# 22_-_SD_CARD_SPI_FLASH_EEPROM.net
KiCad netlist of a schematic drawn in Altium Designer
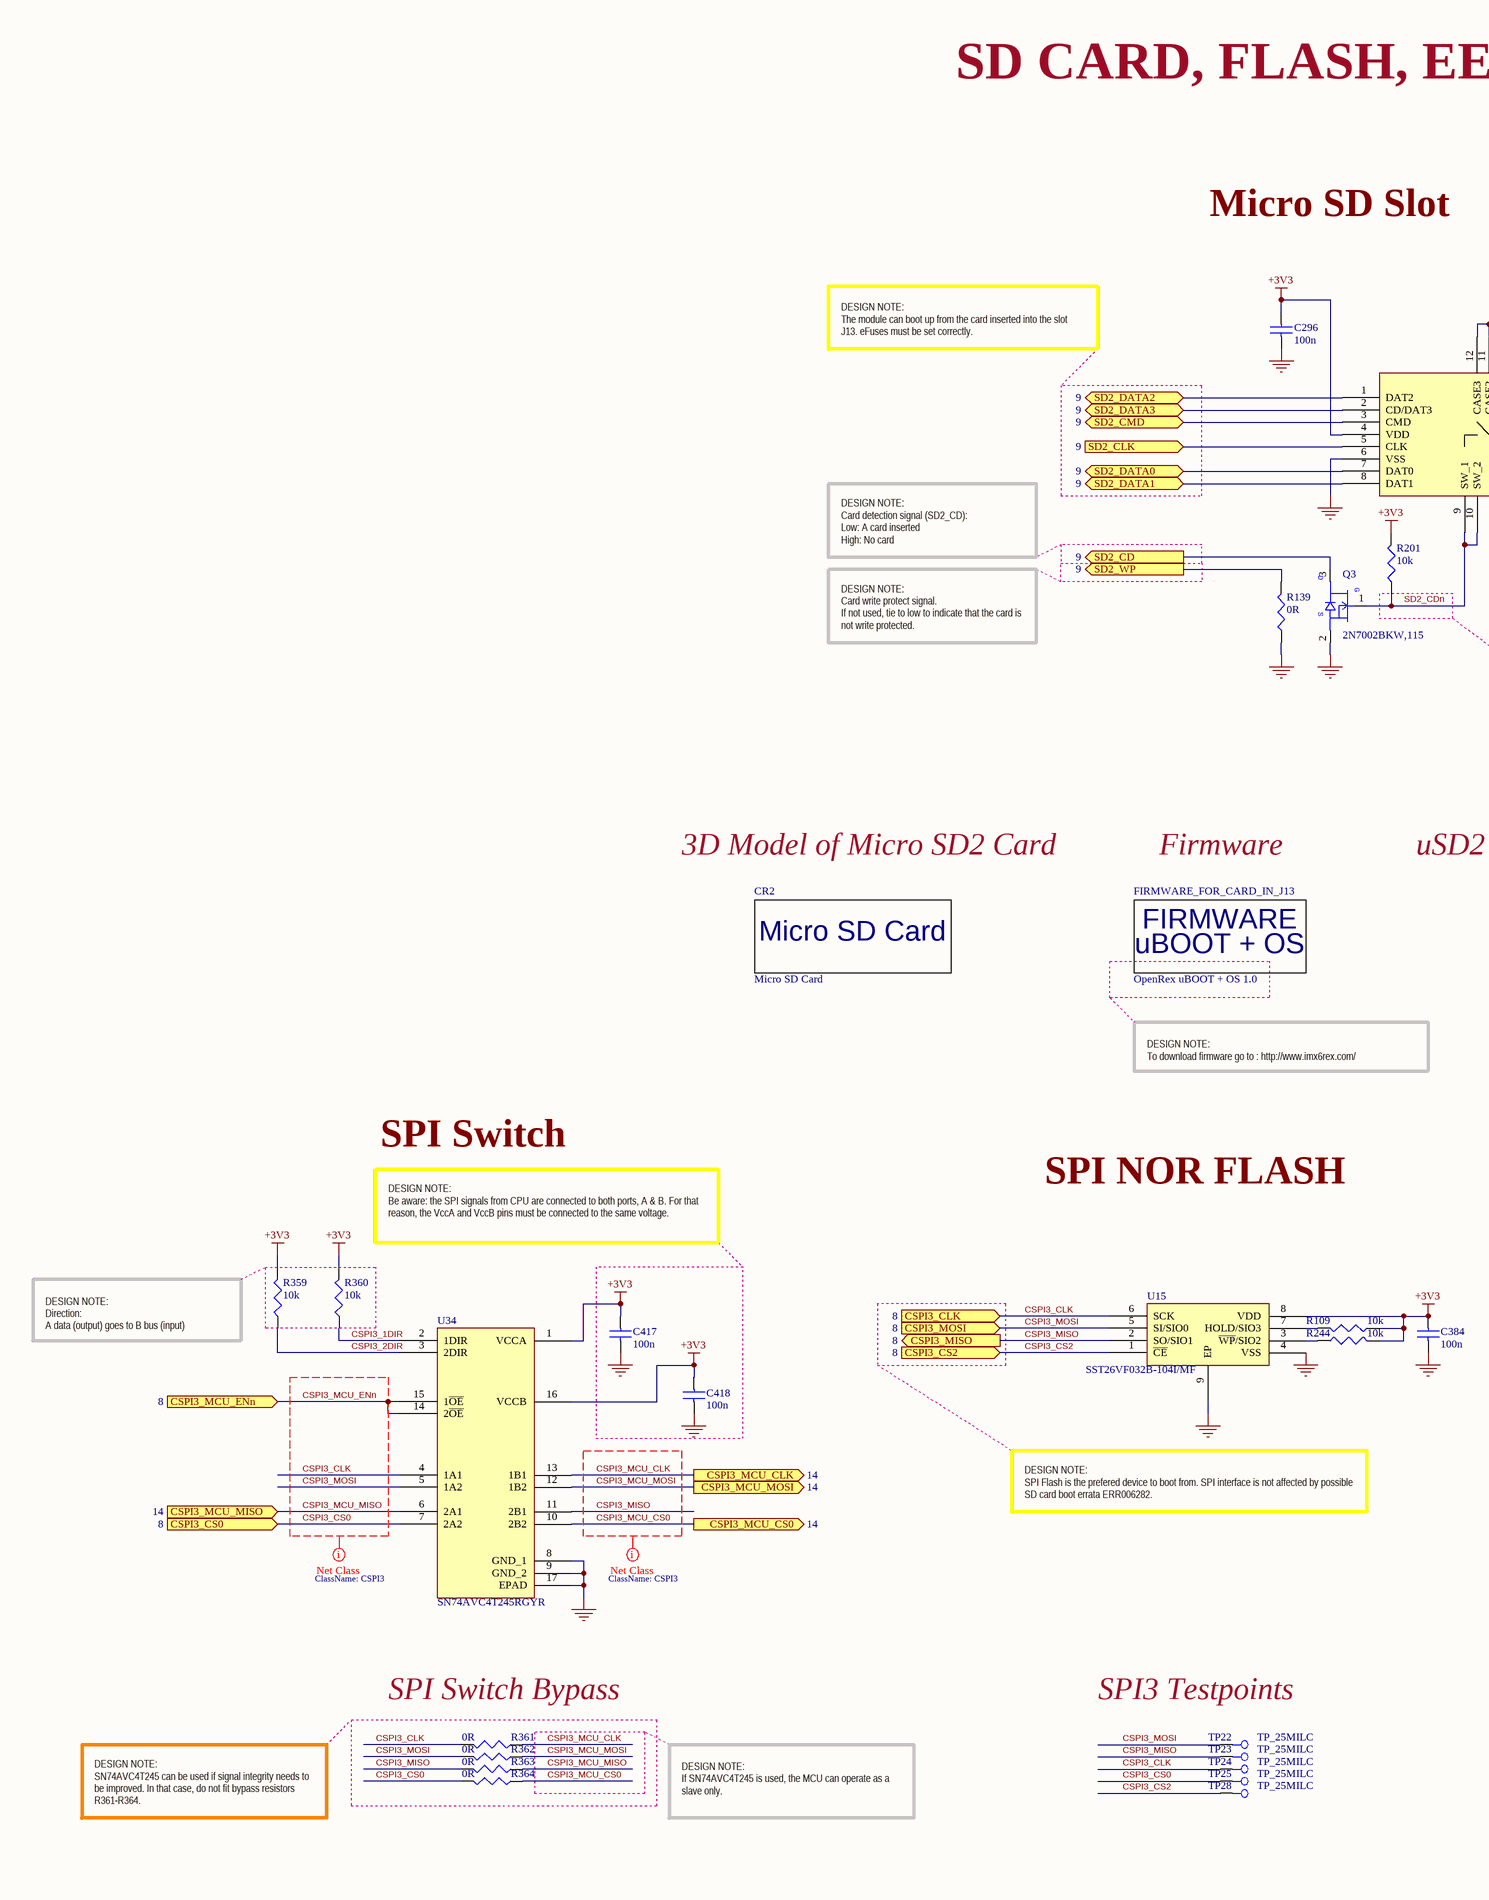
[diagram p0: [22] - SD CARD, SPI, FLASH, EEPROM,.SchDoc, left]
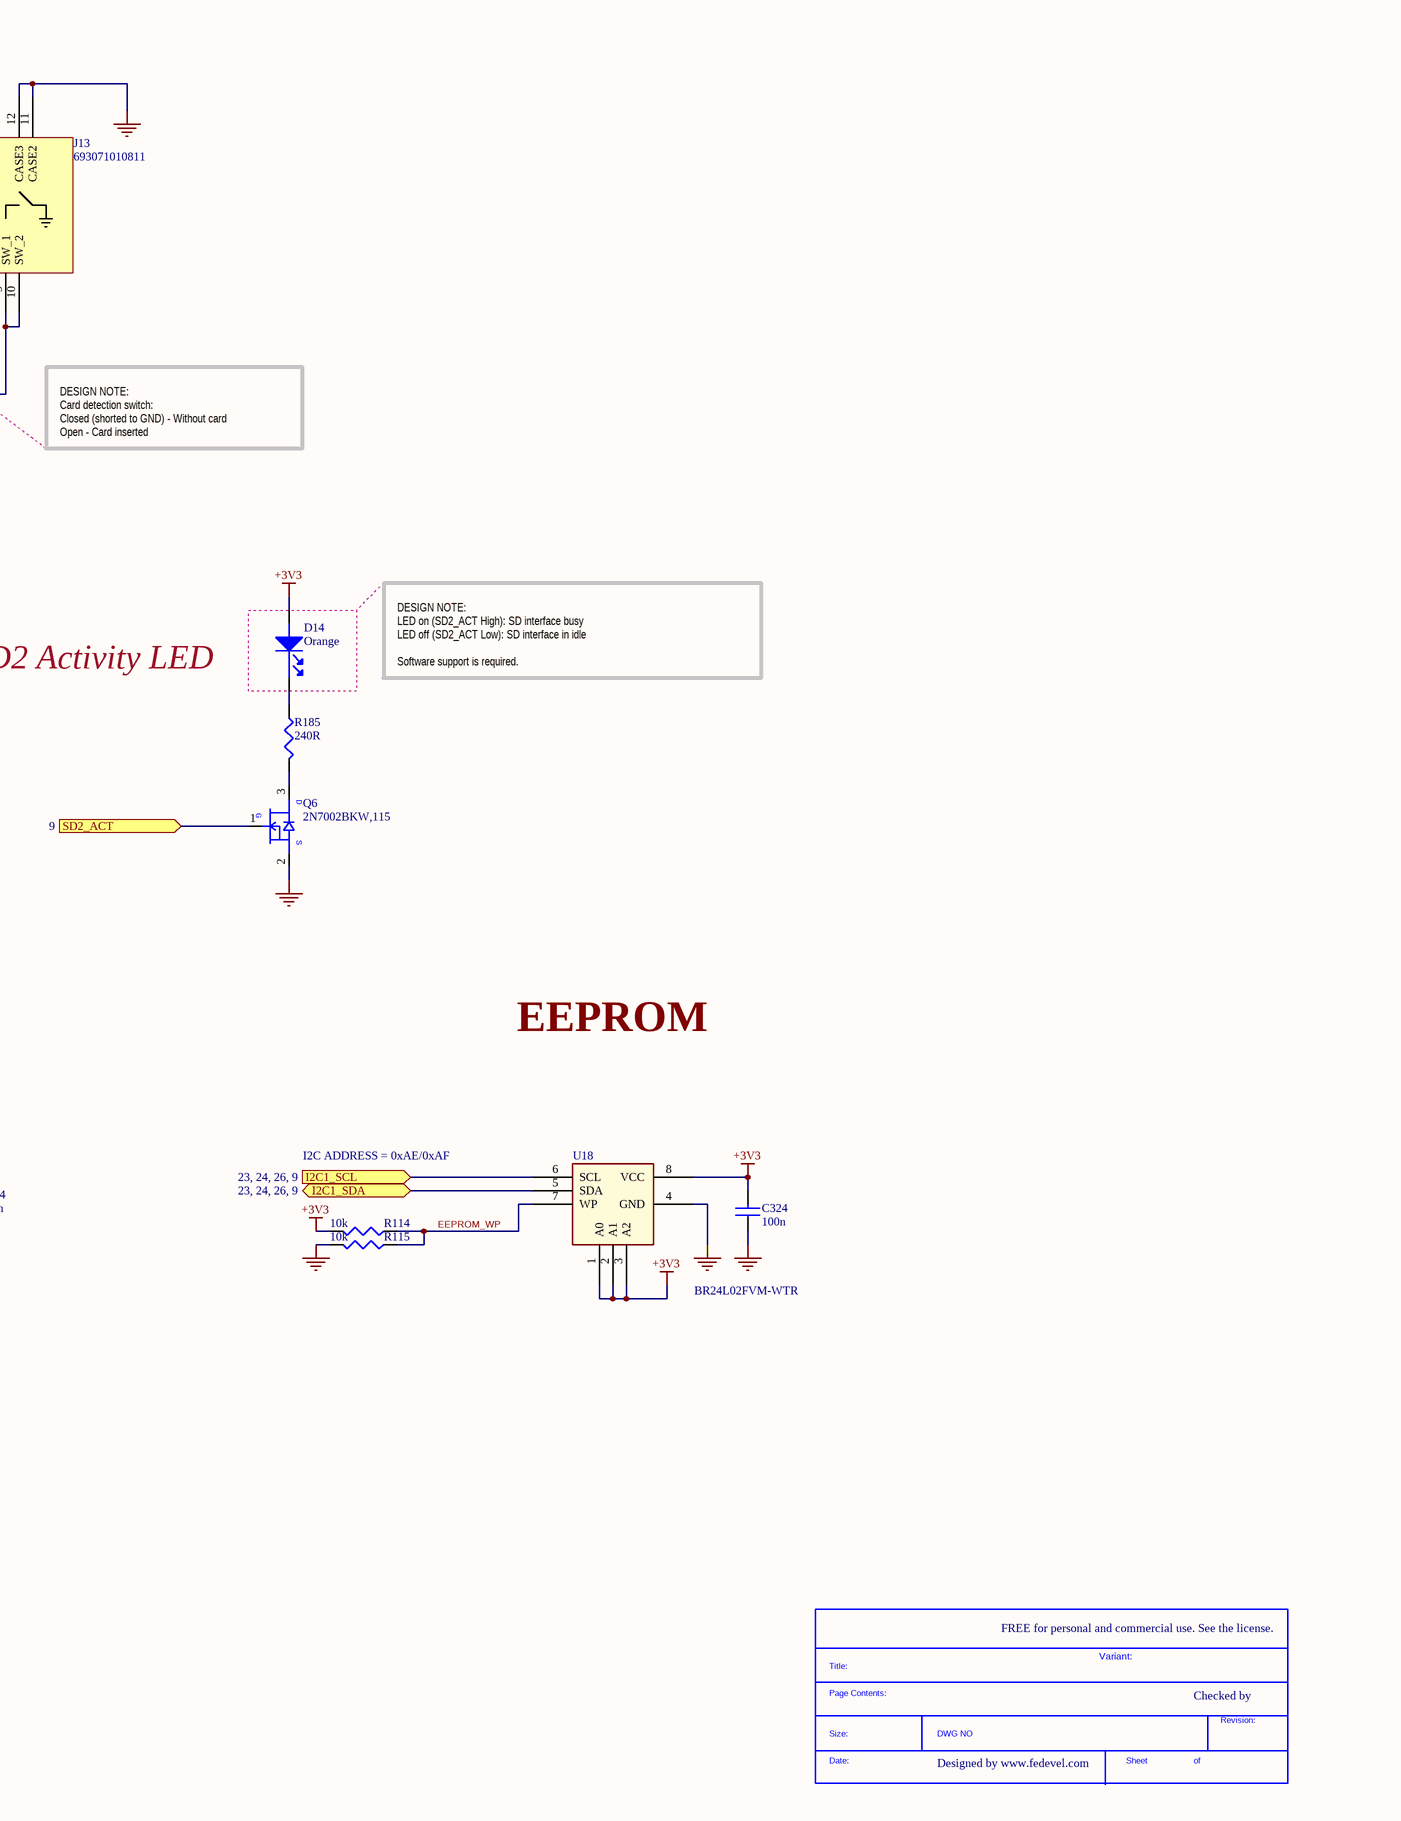
[diagram p1: [22] - SD CARD, SPI, FLASH, EEPROM,.SchDoc, right]

(export (version "E")
  (design (tool "Eeschema 10.0.6"))
  (components
    (comp (ref "C296")
      (value "100n")
      (footprint "C0402")
      (description "CAP CER .10UF 50V X5R 10% 0402")
      (fields
        (field (name "MANUFACTURER") "TDK Corporation")
        (field (name "MANUFACTURER PART NUMBER") "C1005X5R1H104K")
      )
      (libsource (lib "Integrated_Library_FEDEVEL_APR_2015") (part "C1005X5R1H104K"))
    )
    (comp (ref "C324")
      (value "100n")
      (footprint "C0402")
      (description "CAP CER .10UF 50V X5R 10% 0402")
      (fields
        (field (name "MANUFACTURER") "TDK Corporation")
        (field (name "MANUFACTURER PART NUMBER") "C1005X5R1H104K")
      )
      (libsource (lib "Integrated_Library_FEDEVEL_APR_2015") (part "C1005X5R1H104K"))
    )
    (comp (ref "C384")
      (value "100n")
      (footprint "C0402")
      (description "CAP CER .10UF 50V X5R 10% 0402")
      (fields
        (field (name "MANUFACTURER") "TDK Corporation")
        (field (name "MANUFACTURER PART NUMBER") "C1005X5R1H104K")
      )
      (libsource (lib "Integrated_Library_FEDEVEL_APR_2015") (part "C1005X5R1H104K"))
    )
    (comp (ref "C417")
      (value "100n")
      (footprint "C0402")
      (description "CAP CER .10UF 50V X5R 10% 0402")
      (fields
        (field (name "MANUFACTURER") "TDK Corporation")
        (field (name "MANUFACTURER PART NUMBER") "C1005X5R1H104K")
      )
      (libsource (lib "Integrated_Library_FEDEVEL_APR_2015") (part "C1005X5R1H104K"))
    )
    (comp (ref "C418")
      (value "100n")
      (footprint "C0402")
      (description "CAP CER .10UF 50V X5R 10% 0402")
      (fields
        (field (name "MANUFACTURER") "TDK Corporation")
        (field (name "MANUFACTURER PART NUMBER") "C1005X5R1H104K")
      )
      (libsource (lib "Integrated_Library_FEDEVEL_APR_2015") (part "C1005X5R1H104K"))
    )
    (comp (ref "CR2")
      (value "Micro SD Card")
      (footprint "Micro_SD_card")
      (description "Card Micro SD")
      (fields (field (name ".CREATOR") "MM"))
      (libsource (lib "Integrated_Library_FEDEVEL_APR_2015") (part "Card_Micro_SD"))
    )
    (comp (ref "D14")
      (value "Orange")
      (footprint "LED_0603")
      (description "LED SMARTLED ORANGE 606NM 0603")
      (fields
        (field (name "MANUFACTURER") "OSRAM Opto Semiconductors Inc")
        (field (name "MANUFACTURER PART NUMBER") "LO L29K-H2K1-24-Z")
      )
      (libsource (lib "Integrated_Library_FEDEVEL_APR_2015") (part "LO L29K-H2K1-24-Z"))
    )
    (comp (ref "FIRMWARE_FOR_CARD_IN_J13")
      (value "OpenRex uBOOT + OS 1.0")
      (fields (field (name ".CREATOR") "MM") (field (name ".CHECKED SCH") "MM"))
      (libsource (lib "Integrated_Library_FEDEVEL_APR_2015") (part "FIRMWARE_OpenRex_uBOOT_OS 1.0"))
    )
    (comp (ref "J13")
      (value "693071010811")
      (footprint "693071010811")
      (description "CONN MICRO SD 8 POS SMD")
      (fields (field (name "MANUFACTURER") "Wurth Electronics Inc") (field (name ".CREATOR") "MM"))
      (libsource (lib "Integrated_Library_FEDEVEL_APR_2015") (part "693071010811"))
    )
    (comp (ref "Q3")
      (value "2N7002BKW,115")
      (footprint "SC70_SOT323")
      (description "MOSFET N-CH 60V 310MA SOT323")
      (fields (field (name "MANUFACTURER") "NXP Semiconductors"))
      (libsource (lib "Integrated_Library_FEDEVEL_APR_2015") (part "2N7002BKW,115"))
    )
    (comp (ref "Q6")
      (value "2N7002BKW,115")
      (footprint "SC70_SOT323")
      (description "MOSFET N-CH 60V 310MA SOT323")
      (fields (field (name "MANUFACTURER") "NXP Semiconductors"))
      (libsource (lib "Integrated_Library_FEDEVEL_APR_2015") (part "2N7002BKW,115"))
    )
    (comp (ref "R109")
      (value "10k")
      (footprint "R0402")
      (description "RES 10.0K OHM 1/16W 1% 0402 SMD")
      (fields
        (field (name "MANUFACTURER") "Yageo")
        (field (name "MANUFACTURER PART NUMBER") "RC0402FR-0710KL")
      )
      (libsource (lib "Integrated_Library_FEDEVEL_APR_2015") (part "RC0402FR-0710KL"))
    )
    (comp (ref "R114")
      (value "10k")
      (footprint "R0402")
      (description "RES 10.0K OHM 1/16W 1% 0402 SMD")
      (fields
        (field (name "MANUFACTURER") "Yageo")
        (field (name "MANUFACTURER PART NUMBER") "RC0402FR-0710KL")
      )
      (libsource (lib "Integrated_Library_FEDEVEL_APR_2015") (part "RC0402FR-0710KL"))
    )
    (comp (ref "R115")
      (value "10k")
      (footprint "R0402")
      (description "RES 10.0K OHM 1/16W 1% 0402 SMD")
      (fields
        (field (name "MANUFACTURER") "Yageo")
        (field (name "MANUFACTURER PART NUMBER") "RC0402FR-0710KL")
      )
      (libsource (lib "Integrated_Library_FEDEVEL_APR_2015") (part "RC0402FR-0710KL"))
    )
    (comp (ref "R139")
      (value "0R")
      (footprint "R0402")
      (description "RES 0.0 OHM 1/16W 0402 SMD")
      (fields
        (field (name "MANUFACTURER") "Yageo")
        (field (name "MANUFACTURER PART NUMBER") "RC0402JR-070RL")
      )
      (libsource (lib "Integrated_Library_FEDEVEL_APR_2015") (part "RC0402JR-070RL"))
    )
    (comp (ref "R185")
      (value "240R")
      (footprint "R0402")
      (description "RES TF 240 OHM 1% 0.0625W 0402")
      (fields
        (field (name "MANUFACTURER") "Stackpole Electronics Inc")
        (field (name "MANUFACTURER PART NUMBER") "RMCF0402FT240R")
      )
      (libsource (lib "Integrated_Library_FEDEVEL_APR_2015") (part "RMCF0402FT240R"))
    )
    (comp (ref "R201")
      (value "10k")
      (footprint "R0402")
      (description "RES 10.0K OHM 1/16W 1% 0402 SMD")
      (fields
        (field (name "MANUFACTURER") "Yageo")
        (field (name "MANUFACTURER PART NUMBER") "RC0402FR-0710KL")
      )
      (libsource (lib "Integrated_Library_FEDEVEL_APR_2015") (part "RC0402FR-0710KL"))
    )
    (comp (ref "R244")
      (value "10k")
      (footprint "R0402")
      (description "RES 10.0K OHM 1/16W 1% 0402 SMD")
      (fields
        (field (name "MANUFACTURER") "Yageo")
        (field (name "MANUFACTURER PART NUMBER") "RC0402FR-0710KL")
      )
      (libsource (lib "Integrated_Library_FEDEVEL_APR_2015") (part "RC0402FR-0710KL"))
    )
    (comp (ref "R359")
      (value "10k")
      (footprint "R0402")
      (description "RES 10.0K OHM 1/16W 1% 0402 SMD")
      (fields
        (field (name "MANUFACTURER") "Yageo")
        (field (name "MANUFACTURER PART NUMBER") "RC0402FR-0710KL")
      )
      (libsource (lib "Integrated_Library_FEDEVEL_APR_2015") (part "RC0402FR-0710KL"))
    )
    (comp (ref "R360")
      (value "10k")
      (footprint "R0402")
      (description "RES 10.0K OHM 1/16W 1% 0402 SMD")
      (fields
        (field (name "MANUFACTURER") "Yageo")
        (field (name "MANUFACTURER PART NUMBER") "RC0402FR-0710KL")
      )
      (libsource (lib "Integrated_Library_FEDEVEL_APR_2015") (part "RC0402FR-0710KL"))
    )
    (comp (ref "R361")
      (value "0R")
      (footprint "R0402")
      (description "RES 0.0 OHM 1/16W 0402 SMD")
      (fields
        (field (name "MANUFACTURER") "Yageo")
        (field (name "MANUFACTURER PART NUMBER") "RC0402JR-070RL")
      )
      (libsource (lib "Integrated_Library_FEDEVEL_APR_2015") (part "RC0402JR-070RL"))
    )
    (comp (ref "R362")
      (value "0R")
      (footprint "R0402")
      (description "RES 0.0 OHM 1/16W 0402 SMD")
      (fields
        (field (name "MANUFACTURER") "Yageo")
        (field (name "MANUFACTURER PART NUMBER") "RC0402JR-070RL")
      )
      (libsource (lib "Integrated_Library_FEDEVEL_APR_2015") (part "RC0402JR-070RL"))
    )
    (comp (ref "R363")
      (value "0R")
      (footprint "R0402")
      (description "RES 0.0 OHM 1/16W 0402 SMD")
      (fields
        (field (name "MANUFACTURER") "Yageo")
        (field (name "MANUFACTURER PART NUMBER") "RC0402JR-070RL")
      )
      (libsource (lib "Integrated_Library_FEDEVEL_APR_2015") (part "RC0402JR-070RL"))
    )
    (comp (ref "R364")
      (value "0R")
      (footprint "R0402")
      (description "RES 0.0 OHM 1/16W 0402 SMD")
      (fields
        (field (name "MANUFACTURER") "Yageo")
        (field (name "MANUFACTURER PART NUMBER") "RC0402JR-070RL")
      )
      (libsource (lib "Integrated_Library_FEDEVEL_APR_2015") (part "RC0402JR-070RL"))
    )
    (comp (ref "TP22")
      (value "TP_25MILC")
      (footprint "TP_25C")
      (description "Test Point 25mil")
      (libsource (lib "Integrated_Library_FEDEVEL_APR_2015") (part "TP_25MILC"))
    )
    (comp (ref "TP23")
      (value "TP_25MILC")
      (footprint "TP_25C")
      (description "Test Point 25mil")
      (libsource (lib "Integrated_Library_FEDEVEL_APR_2015") (part "TP_25MILC"))
    )
    (comp (ref "TP24")
      (value "TP_25MILC")
      (footprint "TP_25C")
      (description "Test Point 25mil")
      (libsource (lib "Integrated_Library_FEDEVEL_APR_2015") (part "TP_25MILC"))
    )
    (comp (ref "TP25")
      (value "TP_25MILC")
      (footprint "TP_25C")
      (description "Test Point 25mil")
      (libsource (lib "Integrated_Library_FEDEVEL_APR_2015") (part "TP_25MILC"))
    )
    (comp (ref "TP28")
      (value "TP_25MILC")
      (footprint "TP_25C")
      (description "Test Point 25mil")
      (libsource (lib "Integrated_Library_FEDEVEL_APR_2015") (part "TP_25MILC"))
    )
    (comp (ref "U15")
      (value "SST26VF032B-104I/MF")
      (footprint "WSON8_6X5MM")
      (description "IC FLASH 32MBIT")
      (fields
        (field (name "MANUFACTURER") "Microchip Technology")
        (field (name ".CREATOR") "MM")
        (field (name ".CHECKED SCH") "MM")
        (field (name ".CHECKED PCB") "MM, paper model not chceked")
      )
      (libsource (lib "Integrated_Library_FEDEVEL_APR_2015") (part "SST26VF032B-104I/MF"))
    )
    (comp (ref "U18")
      (value "BR24L02FVM-WTR")
      (footprint "MSOP8 _SMALLER")
      (description "IC EEPROM 2KBIT 400KHZ 8MSOP")
      (fields (field (name "MANUFACTURER") "Rohm Semiconductor"))
      (libsource (lib "Integrated_Library_FEDEVEL_APR_2015") (part "BR24L02FVM-WTR"))
    )
    (comp (ref "U34")
      (value "SN74AVC4T245RGYR")
      (footprint "RGY (R-PVQFN-N16)")
      (description "IC BUS TRANSCVR 4BIT 16QFN")
      (fields
        (field (name "MANUFACTURER") "Texas Instruments")
        (field (name ".CREATOR") "MM")
        (field (name ".CHECKED PCB") "MM")
        (field (name ".CHECKED SCH") "MM")
      )
      (libsource (lib "Integrated_Library_FEDEVEL_APR_2015") (part "SN74AVC4T245RGYR"))
    )
  )
  (nets
    (net (code "1") (name "+3V3") (class "Default")
      (node (ref "C296") (pin "1") (pinfunction "1_1") (pintype "passive"))
      (node (ref "C324") (pin "2") (pinfunction "2_2") (pintype "passive"))
      (node (ref "C384") (pin "1") (pinfunction "1_1") (pintype "passive"))
      (node (ref "C417") (pin "1") (pinfunction "1_1") (pintype "passive"))
      (node (ref "C418") (pin "1") (pinfunction "1_1") (pintype "passive"))
      (node (ref "D14") (pin "2") (pinfunction "ANODE_2") (pintype "passive"))
      (node (ref "J13") (pin "4") (pinfunction "VDD_4") (pintype "passive"))
      (node (ref "R109") (pin "1") (pinfunction "1_1") (pintype "passive"))
      (node (ref "R114") (pin "2") (pinfunction "2_2") (pintype "passive"))
      (node (ref "R201") (pin "2") (pinfunction "2_2") (pintype "passive"))
      (node (ref "R244") (pin "2") (pinfunction "2_2") (pintype "passive"))
      (node (ref "R359") (pin "2") (pinfunction "2_2") (pintype "passive"))
      (node (ref "R360") (pin "2") (pinfunction "2_2") (pintype "passive"))
      (node (ref "U15") (pin "8") (pinfunction "VDD_8") (pintype "passive"))
      (node (ref "U18") (pin "1") (pinfunction "A0_1") (pintype "passive"))
      (node (ref "U18") (pin "2") (pinfunction "A1_2") (pintype "passive"))
      (node (ref "U18") (pin "3") (pinfunction "A2_3") (pintype "passive"))
      (node (ref "U18") (pin "8") (pinfunction "VCC_8") (pintype "power_in"))
      (node (ref "U34") (pin "1") (pinfunction "VCCA_1") (pintype "passive"))
      (node (ref "U34") (pin "16") (pinfunction "VCCB_16") (pintype "passive"))
    )
    (net (code "2") (name "/CSPI3_1DIR") (class "Default")
      (node (ref "R360") (pin "1") (pinfunction "1_1") (pintype "passive"))
      (node (ref "U34") (pin "2") (pinfunction "1DIR_2") (pintype "passive"))
    )
    (net (code "3") (name "/CSPI3_2DIR") (class "Default")
      (node (ref "R359") (pin "1") (pinfunction "1_1") (pintype "passive"))
      (node (ref "U34") (pin "3") (pinfunction "2DIR_3") (pintype "passive"))
    )
    (net (code "4") (name "/CSPI3_CLK") (class "Default")
      (node (ref "R361") (pin "2") (pinfunction "2_2") (pintype "passive"))
      (node (ref "TP24") (pin "1") (pinfunction "1_1") (pintype "passive"))
      (node (ref "U15") (pin "6") (pinfunction "SCK_6") (pintype "passive"))
      (node (ref "U34") (pin "4") (pinfunction "1A1_4") (pintype "passive"))
    )
    (net (code "5") (name "/CSPI3_CS0") (class "Default")
      (node (ref "R364") (pin "2") (pinfunction "2_2") (pintype "passive"))
      (node (ref "TP25") (pin "1") (pinfunction "1_1") (pintype "passive"))
      (node (ref "U34") (pin "7") (pinfunction "2A2_7") (pintype "passive"))
    )
    (net (code "6") (name "/CSPI3_CS2") (class "Default")
      (node (ref "TP28") (pin "1") (pinfunction "1_1") (pintype "passive"))
      (node (ref "U15") (pin "1") (pinfunction "~{CE}_1") (pintype "passive"))
    )
    (net (code "7") (name "/CSPI3_MCU_CLK") (class "Default")
      (node (ref "R361") (pin "1") (pinfunction "1_1") (pintype "passive"))
      (node (ref "U34") (pin "13") (pinfunction "1B1_13") (pintype "passive"))
    )
    (net (code "8") (name "/CSPI3_MCU_CS0") (class "Default")
      (node (ref "R364") (pin "1") (pinfunction "1_1") (pintype "passive"))
      (node (ref "U34") (pin "10") (pinfunction "2B2_10") (pintype "passive"))
    )
    (net (code "9") (name "/CSPI3_MCU_ENn") (class "Default")
      (node (ref "U34") (pin "14") (pinfunction "2~{OE}_14") (pintype "passive"))
      (node (ref "U34") (pin "15") (pinfunction "1~{OE}_15") (pintype "passive"))
    )
    (net (code "10") (name "/CSPI3_MCU_MISO") (class "Default")
      (node (ref "R363") (pin "1") (pinfunction "1_1") (pintype "passive"))
      (node (ref "U34") (pin "6") (pinfunction "2A1_6") (pintype "passive"))
    )
    (net (code "11") (name "/CSPI3_MCU_MOSI") (class "Default")
      (node (ref "R362") (pin "1") (pinfunction "1_1") (pintype "passive"))
      (node (ref "U34") (pin "12") (pinfunction "1B2_12") (pintype "passive"))
    )
    (net (code "12") (name "/CSPI3_MISO") (class "Default")
      (node (ref "R363") (pin "2") (pinfunction "2_2") (pintype "passive"))
      (node (ref "TP23") (pin "1") (pinfunction "1_1") (pintype "passive"))
      (node (ref "U15") (pin "2") (pinfunction "SO/SIO1_2") (pintype "passive"))
      (node (ref "U34") (pin "11") (pinfunction "2B1_11") (pintype "passive"))
    )
    (net (code "13") (name "/CSPI3_MOSI") (class "Default")
      (node (ref "R362") (pin "2") (pinfunction "2_2") (pintype "passive"))
      (node (ref "TP22") (pin "1") (pinfunction "1_1") (pintype "passive"))
      (node (ref "U15") (pin "5") (pinfunction "SI/SIO0_5") (pintype "passive"))
      (node (ref "U34") (pin "5") (pinfunction "1A2_5") (pintype "passive"))
    )
    (net (code "14") (name "/EEPROM_WP") (class "Default")
      (node (ref "R114") (pin "1") (pinfunction "1_1") (pintype "passive"))
      (node (ref "R115") (pin "1") (pinfunction "1_1") (pintype "passive"))
      (node (ref "U18") (pin "7") (pinfunction "WP_7") (pintype "passive"))
    )
    (net (code "15") (name "/I2C1_SCL") (class "Default")
      (node (ref "U18") (pin "6") (pinfunction "SCL_6") (pintype "passive"))
    )
    (net (code "16") (name "/I2C1_SDA") (class "Default")
      (node (ref "U18") (pin "5") (pinfunction "SDA_5") (pintype "passive"))
    )
    (net (code "17") (name "/SD2_ACT") (class "Default")
      (node (ref "Q6") (pin "1") (pinfunction "GATE_1") (pintype "passive"))
    )
    (net (code "18") (name "/SD2_CD") (class "Default")
      (node (ref "Q3") (pin "3") (pinfunction "DRAIN_3") (pintype "passive"))
    )
    (net (code "19") (name "/SD2_CDn") (class "Default")
      (node (ref "J13") (pin "10") (pinfunction "SW_2_10") (pintype "passive"))
      (node (ref "J13") (pin "9") (pinfunction "SW_1_9") (pintype "passive"))
      (node (ref "Q3") (pin "1") (pinfunction "GATE_1") (pintype "passive"))
      (node (ref "R201") (pin "1") (pinfunction "1_1") (pintype "passive"))
    )
    (net (code "20") (name "/SD2_CLK") (class "Default")
      (node (ref "J13") (pin "5") (pinfunction "CLK_5") (pintype "passive"))
    )
    (net (code "21") (name "/SD2_CMD") (class "Default")
      (node (ref "J13") (pin "3") (pinfunction "CMD_3") (pintype "passive"))
    )
    (net (code "22") (name "/SD2_DATA0") (class "Default")
      (node (ref "J13") (pin "7") (pinfunction "DAT0_7") (pintype "passive"))
    )
    (net (code "23") (name "/SD2_DATA1") (class "Default")
      (node (ref "J13") (pin "8") (pinfunction "DAT1_8") (pintype "passive"))
    )
    (net (code "24") (name "/SD2_DATA2") (class "Default")
      (node (ref "J13") (pin "1") (pinfunction "DAT2_1") (pintype "passive"))
    )
    (net (code "25") (name "/SD2_DATA3") (class "Default")
      (node (ref "J13") (pin "2") (pinfunction "CD/DAT3_2") (pintype "passive"))
    )
    (net (code "26") (name "/SD2_WP") (class "Default")
      (node (ref "R139") (pin "2") (pinfunction "2_2") (pintype "passive"))
    )
    (net (code "27") (name "GND") (class "Default")
      (node (ref "C296") (pin "2") (pinfunction "2_2") (pintype "passive"))
      (node (ref "C324") (pin "1") (pinfunction "1_1") (pintype "passive"))
      (node (ref "C384") (pin "2") (pinfunction "2_2") (pintype "passive"))
      (node (ref "C417") (pin "2") (pinfunction "2_2") (pintype "passive"))
      (node (ref "C418") (pin "2") (pinfunction "2_2") (pintype "passive"))
      (node (ref "J13") (pin "11") (pinfunction "CASE2_11") (pintype "passive"))
      (node (ref "J13") (pin "12") (pinfunction "CASE3_12") (pintype "passive"))
      (node (ref "J13") (pin "6") (pinfunction "VSS_6") (pintype "passive"))
      (node (ref "Q3") (pin "2") (pinfunction "SOURCE_2") (pintype "passive"))
      (node (ref "Q6") (pin "2") (pinfunction "SOURCE_2") (pintype "passive"))
      (node (ref "R115") (pin "2") (pinfunction "2_2") (pintype "passive"))
      (node (ref "R139") (pin "1") (pinfunction "1_1") (pintype "passive"))
      (node (ref "U15") (pin "4") (pinfunction "VSS_4") (pintype "passive"))
      (node (ref "U15") (pin "9") (pinfunction "EP_9") (pintype "passive"))
      (node (ref "U18") (pin "4") (pinfunction "GND_4") (pintype "power_in"))
      (node (ref "U34") (pin "17") (pinfunction "EPAD_17") (pintype "passive"))
      (node (ref "U34") (pin "8") (pinfunction "GND_1_8") (pintype "passive"))
      (node (ref "U34") (pin "9") (pinfunction "GND_2_9") (pintype "passive"))
    )
    (net (code "28") (name "Net-(D14-cathode)") (class "Default")
      (node (ref "D14") (pin "1") (pinfunction "cathode_1") (pintype "passive"))
      (node (ref "R185") (pin "1") (pinfunction "1_1") (pintype "passive"))
    )
    (net (code "29") (name "Net-(Q6-DRAIN)") (class "Default")
      (node (ref "Q6") (pin "3") (pinfunction "DRAIN_3") (pintype "passive"))
      (node (ref "R185") (pin "2") (pinfunction "2_2") (pintype "passive"))
    )
    (net (code "30") (name "Net-(U15-HOLD{slash}SIO3)") (class "Default")
      (node (ref "R109") (pin "2") (pinfunction "2_2") (pintype "passive"))
      (node (ref "U15") (pin "7") (pinfunction "HOLD/SIO3_7") (pintype "passive"))
    )
    (net (code "31") (name "Net-(U15-~{WP}{slash}SIO2)") (class "Default")
      (node (ref "R244") (pin "1") (pinfunction "1_1") (pintype "passive"))
      (node (ref "U15") (pin "3") (pinfunction "~{WP}/SIO2_3") (pintype "passive"))
    )
  )
)
